# tweeq-Proto.net
KiCad netlist of a schematic drawn in EAGLE
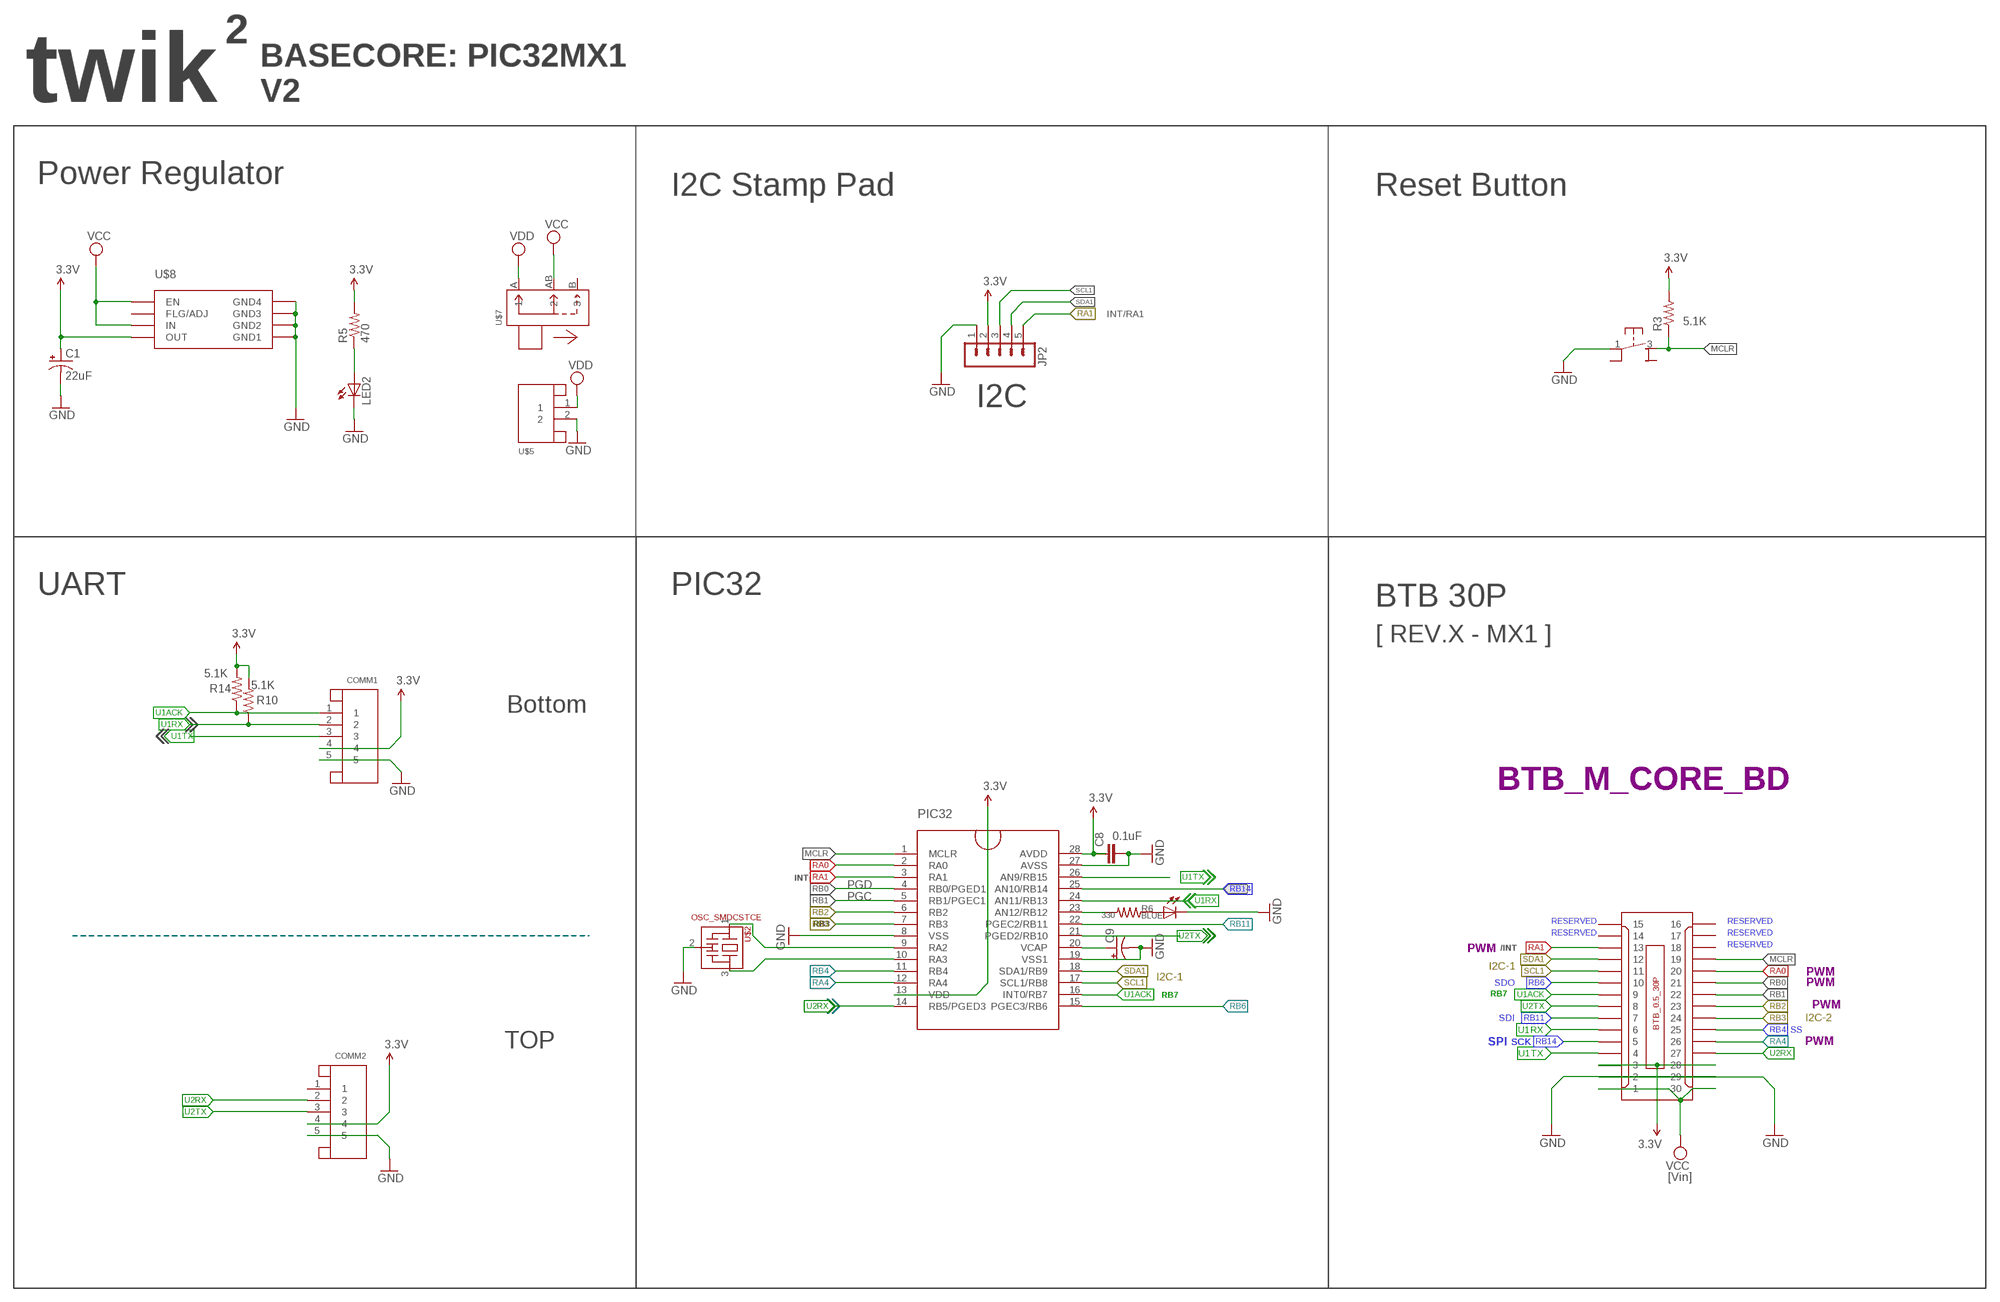
[diagram p0: schematic, sheet 1]

(export (version "E")
  (design (tool "Eeschema 10.0.6"))
  (components
    (comp (ref "C1")
      (value "22uF")
      (footprint "eagle-import:SMC_B")
      (libsource (lib "eagle-import") (part "CPOL-USSMCB"))
    )
    (comp (ref "C8")
      (value "0.1uF")
      (footprint "eagle-import:C0402K")
      (libsource (lib "eagle-import") (part "C-EUC0402K"))
    )
    (comp (ref "C9")
      (value "CPOL-USA/3216-18R")
      (footprint "eagle-import:A_3216-18R")
      (libsource (lib "eagle-import") (part "CPOL-USA/3216-18R"))
    )
    (comp (ref "COMM1")
      (value "JST-5PINSH")
      (footprint "eagle-import:SH1.0-5PIN")
      (libsource (lib "eagle-import") (part "JST-5PINSH"))
    )
    (comp (ref "COMM2")
      (value "JST-5PINSH")
      (footprint "eagle-import:SH1.0-5PIN")
      (libsource (lib "eagle-import") (part "JST-5PINSH"))
    )
    (comp (ref "JP2")
      (value "M05-11.5MM-SMT")
      (footprint "eagle-import:1X05-1.5MM-SMT")
      (libsource (lib "eagle-import") (part "M05-11.5MM-SMT"))
    )
    (comp (ref "LED2")
      (value "LEDCHIP-LED0805")
      (footprint "eagle-import:CHIP-LED0805")
      (libsource (lib "eagle-import") (part "LEDCHIP-LED0805"))
    )
    (comp (ref "PIC32")
      (value "PIC32MX_1XX_2XX")
      (footprint "eagle-import:SSOP28")
      (libsource (lib "eagle-import") (part "PIC32MX_1XX_2XX"))
    )
    (comp (ref "PIC_LED")
      (value "BLUE")
      (footprint "eagle-import:CHIP-LED0805")
      (libsource (lib "eagle-import") (part "LEDCHIP-LED0805"))
    )
    (comp (ref "R3")
      (value "5.1K")
      (footprint "eagle-import:R0402")
      (libsource (lib "eagle-import") (part "R-US_R0402"))
    )
    (comp (ref "R5")
      (value "470")
      (footprint "eagle-import:R0402")
      (libsource (lib "eagle-import") (part "R-US_R0402"))
    )
    (comp (ref "R6")
      (value "330")
      (footprint "eagle-import:R0402")
      (libsource (lib "eagle-import") (part "R-US_R0402"))
    )
    (comp (ref "R10")
      (value "5.1K")
      (footprint "eagle-import:R0402")
      (libsource (lib "eagle-import") (part "R-US_R0402"))
    )
    (comp (ref "R14")
      (value "5.1K")
      (footprint "eagle-import:R0402")
      (libsource (lib "eagle-import") (part "R-US_R0402"))
    )
    (comp (ref "U$1")
      (value "BTB_CONN_30P/M")
      (footprint "eagle-import:BTB0.5-30M-3.0G")
      (libsource (lib "eagle-import") (part "BTB_CONN_30P/M"))
    )
    (comp (ref "U$2")
      (value "OSC_SMDCSTCE")
      (footprint "eagle-import:CSTCE_RESONATOR_SMD")
      (libsource (lib "eagle-import") (part "OSC_SMDCSTCE"))
    )
    (comp (ref "U$4")
      (value "PB_MICRO_SMT")
      (footprint "eagle-import:PB_SMT_3.5X3X2")
      (libsource (lib "eagle-import") (part "PB_MICRO_SMT"))
    )
    (comp (ref "U$5")
      (value "JST-2PINSH")
      (footprint "eagle-import:SH1.0-2PIN")
      (libsource (lib "eagle-import") (part "JST-2PINSH"))
    )
    (comp (ref "U$7")
      (value "SLIDE_SWITCH_MINI/MSK1101")
      (footprint "eagle-import:MSK1101")
      (libsource (lib "eagle-import") (part "SLIDE_SWITCH_MINI/MSK1101"))
    )
    (comp (ref "U$8")
      (value "MIC5239-MM")
      (footprint "eagle-import:MSOP8")
      (libsource (lib "eagle-import") (part "MIC5239-MM"))
    )
  )
  (nets
    (net (code "1") (name "3.3V") (class "Default")
      (node (ref "C1") (pin "+") (pinfunction "+_+") (pintype "passive"))
      (node (ref "C8") (pin "1") (pinfunction "1_1") (pintype "passive"))
      (node (ref "COMM1") (pin "4") (pinfunction "4_4") (pintype "bidirectional"))
      (node (ref "COMM2") (pin "4") (pinfunction "4_4") (pintype "bidirectional"))
      (node (ref "JP2") (pin "2") (pinfunction "2_2") (pintype "passive"))
      (node (ref "PIC32") (pin "13") (pinfunction "VDD_13") (pintype "bidirectional"))
      (node (ref "PIC32") (pin "28") (pinfunction "AVDD_28") (pintype "bidirectional"))
      (node (ref "R10") (pin "2") (pinfunction "2_2") (pintype "passive"))
      (node (ref "R14") (pin "2") (pinfunction "2_2") (pintype "passive"))
      (node (ref "R3") (pin "2") (pinfunction "2_2") (pintype "passive"))
      (node (ref "R5") (pin "2") (pinfunction "2_2") (pintype "passive"))
      (node (ref "U$1") (pin "28") (pinfunction "28_28") (pintype "bidirectional"))
      (node (ref "U$1") (pin "3") (pinfunction "3_3") (pintype "bidirectional"))
      (node (ref "U$8") (pin "4") (pinfunction "OUT_4") (pintype "bidirectional"))
    )
    (net (code "2") (name "GND") (class "Default")
      (node (ref "C1") (pin "-") (pinfunction "-_-") (pintype "passive"))
      (node (ref "C8") (pin "2") (pinfunction "2_2") (pintype "passive"))
      (node (ref "C9") (pin "-") (pinfunction "-_-") (pintype "passive"))
      (node (ref "COMM1") (pin "5") (pinfunction "5_5") (pintype "bidirectional"))
      (node (ref "COMM2") (pin "5") (pinfunction "5_5") (pintype "bidirectional"))
      (node (ref "JP2") (pin "1") (pinfunction "1_1") (pintype "passive"))
      (node (ref "LED2") (pin "C") (pinfunction "C_C") (pintype "passive"))
      (node (ref "PIC32") (pin "19") (pinfunction "VSS1_19") (pintype "bidirectional"))
      (node (ref "PIC32") (pin "27") (pinfunction "AVSS_27") (pintype "bidirectional"))
      (node (ref "PIC32") (pin "8") (pinfunction "VSS_8") (pintype "bidirectional"))
      (node (ref "PIC_LED") (pin "C") (pinfunction "C_C") (pintype "passive"))
      (node (ref "U$1") (pin "2") (pinfunction "2_2") (pintype "bidirectional"))
      (node (ref "U$1") (pin "29") (pinfunction "29_29") (pintype "bidirectional"))
      (node (ref "U$2") (pin "2") (pinfunction "VSS_2") (pintype "power_in"))
      (node (ref "U$4") (pin "1") (pinfunction "1_1") (pintype "passive"))
      (node (ref "U$5") (pin "2") (pinfunction "2_2") (pintype "bidirectional"))
      (node (ref "U$8") (pin "5") (pinfunction "GND1_5") (pintype "bidirectional"))
      (node (ref "U$8") (pin "6") (pinfunction "GND2_6") (pintype "bidirectional"))
      (node (ref "U$8") (pin "7") (pinfunction "GND3_7") (pintype "bidirectional"))
      (node (ref "U$8") (pin "8") (pinfunction "GND4_8") (pintype "bidirectional"))
    )
    (net (code "3") (name "MCLR") (class "Default")
      (node (ref "PIC32") (pin "1") (pinfunction "MCLR_1") (pintype "bidirectional"))
      (node (ref "R3") (pin "1") (pinfunction "1_1") (pintype "passive"))
      (node (ref "U$1") (pin "19") (pinfunction "19_19") (pintype "bidirectional"))
      (node (ref "U$4") (pin "3") (pinfunction "3_3") (pintype "passive"))
    )
    (net (code "4") (name "Net-(LED2-PadA)") (class "Default")
      (node (ref "LED2") (pin "A") (pinfunction "A_A") (pintype "passive"))
      (node (ref "R5") (pin "1") (pinfunction "1_1") (pintype "passive"))
    )
    (net (code "5") (name "Net-(PIC32-AN12{slash}RB12)") (class "Default")
      (node (ref "PIC32") (pin "23") (pinfunction "AN12/RB12_23") (pintype "bidirectional"))
      (node (ref "R6") (pin "2") (pinfunction "2_2") (pintype "passive"))
    )
    (net (code "6") (name "Net-(PIC32-RA2)") (class "Default")
      (node (ref "PIC32") (pin "9") (pinfunction "RA2_9") (pintype "bidirectional"))
      (node (ref "U$2") (pin "1") (pinfunction "1_1") (pintype "output"))
    )
    (net (code "7") (name "Net-(PIC32-RA3)") (class "Default")
      (node (ref "PIC32") (pin "10") (pinfunction "RA3_10") (pintype "bidirectional"))
      (node (ref "U$2") (pin "3") (pinfunction "3_3") (pintype "input"))
    )
    (net (code "8") (name "Net-(PIC32-VCAP)") (class "Default")
      (node (ref "C9") (pin "+") (pinfunction "+_+") (pintype "passive"))
      (node (ref "PIC32") (pin "20") (pinfunction "VCAP_20") (pintype "bidirectional"))
    )
    (net (code "9") (name "Net-(PIC_LED-PadA)") (class "Default")
      (node (ref "PIC_LED") (pin "A") (pinfunction "A_A") (pintype "passive"))
      (node (ref "R6") (pin "1") (pinfunction "1_1") (pintype "passive"))
    )
    (net (code "10") (name "RA0") (class "Default")
      (node (ref "PIC32") (pin "2") (pinfunction "RA0_2") (pintype "bidirectional"))
      (node (ref "U$1") (pin "20") (pinfunction "20_20") (pintype "bidirectional"))
    )
    (net (code "11") (name "RA1") (class "Default")
      (node (ref "JP2") (pin "5") (pinfunction "5_5") (pintype "passive"))
      (node (ref "PIC32") (pin "3") (pinfunction "RA1_3") (pintype "bidirectional"))
      (node (ref "U$1") (pin "13") (pinfunction "13_13") (pintype "bidirectional"))
    )
    (net (code "12") (name "RA4") (class "Default")
      (node (ref "PIC32") (pin "12") (pinfunction "RA4_12") (pintype "bidirectional"))
      (node (ref "U$1") (pin "26") (pinfunction "26_26") (pintype "bidirectional"))
    )
    (net (code "13") (name "RB0") (class "Default")
      (node (ref "PIC32") (pin "4") (pinfunction "RB0/PGED1_4") (pintype "bidirectional"))
      (node (ref "U$1") (pin "21") (pinfunction "21_21") (pintype "bidirectional"))
    )
    (net (code "14") (name "RB1") (class "Default")
      (node (ref "PIC32") (pin "5") (pinfunction "RB1/PGEC1_5") (pintype "bidirectional"))
      (node (ref "U$1") (pin "22") (pinfunction "22_22") (pintype "bidirectional"))
    )
    (net (code "15") (name "RB2") (class "Default")
      (node (ref "PIC32") (pin "6") (pinfunction "RB2_6") (pintype "bidirectional"))
      (node (ref "U$1") (pin "23") (pinfunction "23_23") (pintype "bidirectional"))
    )
    (net (code "16") (name "RB3") (class "Default")
      (node (ref "PIC32") (pin "7") (pinfunction "RB3_7") (pintype "bidirectional"))
      (node (ref "U$1") (pin "24") (pinfunction "24_24") (pintype "bidirectional"))
    )
    (net (code "17") (name "RB4") (class "Default")
      (node (ref "PIC32") (pin "11") (pinfunction "RB4_11") (pintype "bidirectional"))
      (node (ref "U$1") (pin "25") (pinfunction "25_25") (pintype "bidirectional"))
    )
    (net (code "18") (name "RB6") (class "Default")
      (node (ref "PIC32") (pin "15") (pinfunction "PGEC3/RB6_15") (pintype "bidirectional"))
      (node (ref "U$1") (pin "10") (pinfunction "10_10") (pintype "bidirectional"))
    )
    (net (code "19") (name "RB11") (class "Default")
      (node (ref "PIC32") (pin "22") (pinfunction "PGEC2/RB11_22") (pintype "bidirectional"))
      (node (ref "U$1") (pin "7") (pinfunction "7_7") (pintype "bidirectional"))
    )
    (net (code "20") (name "RB14") (class "Default")
      (node (ref "PIC32") (pin "25") (pinfunction "AN10/RB14_25") (pintype "bidirectional"))
      (node (ref "U$1") (pin "5") (pinfunction "5_5") (pintype "bidirectional"))
    )
    (net (code "21") (name "SCL1") (class "Default")
      (node (ref "JP2") (pin "3") (pinfunction "3_3") (pintype "passive"))
      (node (ref "PIC32") (pin "17") (pinfunction "SCL1/RB8_17") (pintype "bidirectional"))
      (node (ref "U$1") (pin "11") (pinfunction "11_11") (pintype "bidirectional"))
    )
    (net (code "22") (name "SDA1") (class "Default")
      (node (ref "JP2") (pin "4") (pinfunction "4_4") (pintype "passive"))
      (node (ref "PIC32") (pin "18") (pinfunction "SDA1/RB9_18") (pintype "bidirectional"))
      (node (ref "U$1") (pin "12") (pinfunction "12_12") (pintype "bidirectional"))
    )
    (net (code "23") (name "U1ACK") (class "Default")
      (node (ref "COMM1") (pin "1") (pinfunction "1_1") (pintype "bidirectional"))
      (node (ref "PIC32") (pin "16") (pinfunction "INT0/RB7_16") (pintype "bidirectional"))
      (node (ref "R14") (pin "1") (pinfunction "1_1") (pintype "passive"))
      (node (ref "U$1") (pin "9") (pinfunction "9_9") (pintype "bidirectional"))
    )
    (net (code "24") (name "U1RX") (class "Default")
      (node (ref "COMM1") (pin "2") (pinfunction "2_2") (pintype "bidirectional"))
      (node (ref "PIC32") (pin "24") (pinfunction "AN11/RB13_24") (pintype "bidirectional"))
      (node (ref "R10") (pin "1") (pinfunction "1_1") (pintype "passive"))
      (node (ref "U$1") (pin "6") (pinfunction "6_6") (pintype "bidirectional"))
    )
    (net (code "25") (name "U1TX") (class "Default")
      (node (ref "COMM1") (pin "3") (pinfunction "3_3") (pintype "bidirectional"))
      (node (ref "PIC32") (pin "26") (pinfunction "AN9/RB15_26") (pintype "bidirectional"))
      (node (ref "U$1") (pin "4") (pinfunction "4_4") (pintype "bidirectional"))
    )
    (net (code "26") (name "U2RX") (class "Default")
      (node (ref "COMM2") (pin "2") (pinfunction "2_2") (pintype "bidirectional"))
      (node (ref "PIC32") (pin "14") (pinfunction "RB5/PGED3_14") (pintype "bidirectional"))
      (node (ref "U$1") (pin "27") (pinfunction "27_27") (pintype "bidirectional"))
    )
    (net (code "27") (name "U2TX") (class "Default")
      (node (ref "COMM2") (pin "3") (pinfunction "3_3") (pintype "bidirectional"))
      (node (ref "PIC32") (pin "21") (pinfunction "PGED2/RB10_21") (pintype "bidirectional"))
      (node (ref "U$1") (pin "8") (pinfunction "8_8") (pintype "bidirectional"))
    )
    (net (code "28") (name "VCC") (class "Default")
      (node (ref "U$1") (pin "1") (pinfunction "1_1") (pintype "bidirectional"))
      (node (ref "U$1") (pin "30") (pinfunction "30_30") (pintype "bidirectional"))
      (node (ref "U$7") (pin "AB") (pinfunction "2_AB") (pintype "bidirectional"))
      (node (ref "U$8") (pin "1") (pinfunction "EN_1") (pintype "bidirectional"))
      (node (ref "U$8") (pin "3") (pinfunction "IN_3") (pintype "bidirectional"))
    )
    (net (code "29") (name "VDD") (class "Default")
      (node (ref "U$5") (pin "1") (pinfunction "1_1") (pintype "bidirectional"))
      (node (ref "U$7") (pin "A") (pinfunction "1_A") (pintype "bidirectional"))
    )
    (net (code "30") (name "unconnected-(COMM2-Pad1)") (class "Default")
      (node (ref "COMM2") (pin "1") (pinfunction "1_1") (pintype "bidirectional"))
    )
    (net (code "31") (name "unconnected-(U$1-Pad14)") (class "Default")
      (node (ref "U$1") (pin "14") (pinfunction "14_14") (pintype "bidirectional"))
    )
    (net (code "32") (name "unconnected-(U$1-Pad15)") (class "Default")
      (node (ref "U$1") (pin "15") (pinfunction "15_15") (pintype "bidirectional"))
    )
    (net (code "33") (name "unconnected-(U$1-Pad16)") (class "Default")
      (node (ref "U$1") (pin "16") (pinfunction "16_16") (pintype "bidirectional"))
    )
    (net (code "34") (name "unconnected-(U$1-Pad17)") (class "Default")
      (node (ref "U$1") (pin "17") (pinfunction "17_17") (pintype "bidirectional"))
    )
    (net (code "35") (name "unconnected-(U$1-Pad18)") (class "Default")
      (node (ref "U$1") (pin "18") (pinfunction "18_18") (pintype "bidirectional"))
    )
    (net (code "36") (name "unconnected-(U$4-Pad2)") (class "Default")
      (node (ref "U$4") (pin "2") (pinfunction "2_2") (pintype "passive"))
    )
    (net (code "37") (name "unconnected-(U$4-Pad4)") (class "Default")
      (node (ref "U$4") (pin "4") (pinfunction "4_4") (pintype "passive"))
    )
    (net (code "38") (name "unconnected-(U$7-3-PadB)") (class "Default")
      (node (ref "U$7") (pin "B") (pinfunction "3_B") (pintype "bidirectional"))
    )
    (net (code "39") (name "unconnected-(U$8-FLG{slash}ADJ-Pad2)") (class "Default")
      (node (ref "U$8") (pin "2") (pinfunction "FLG/ADJ_2") (pintype "bidirectional"))
    )
  )
)
